# FLASH_S29GL256N11FFIV10_16Mx16.net
KiCad netlist of a schematic drawn in Altium Designer
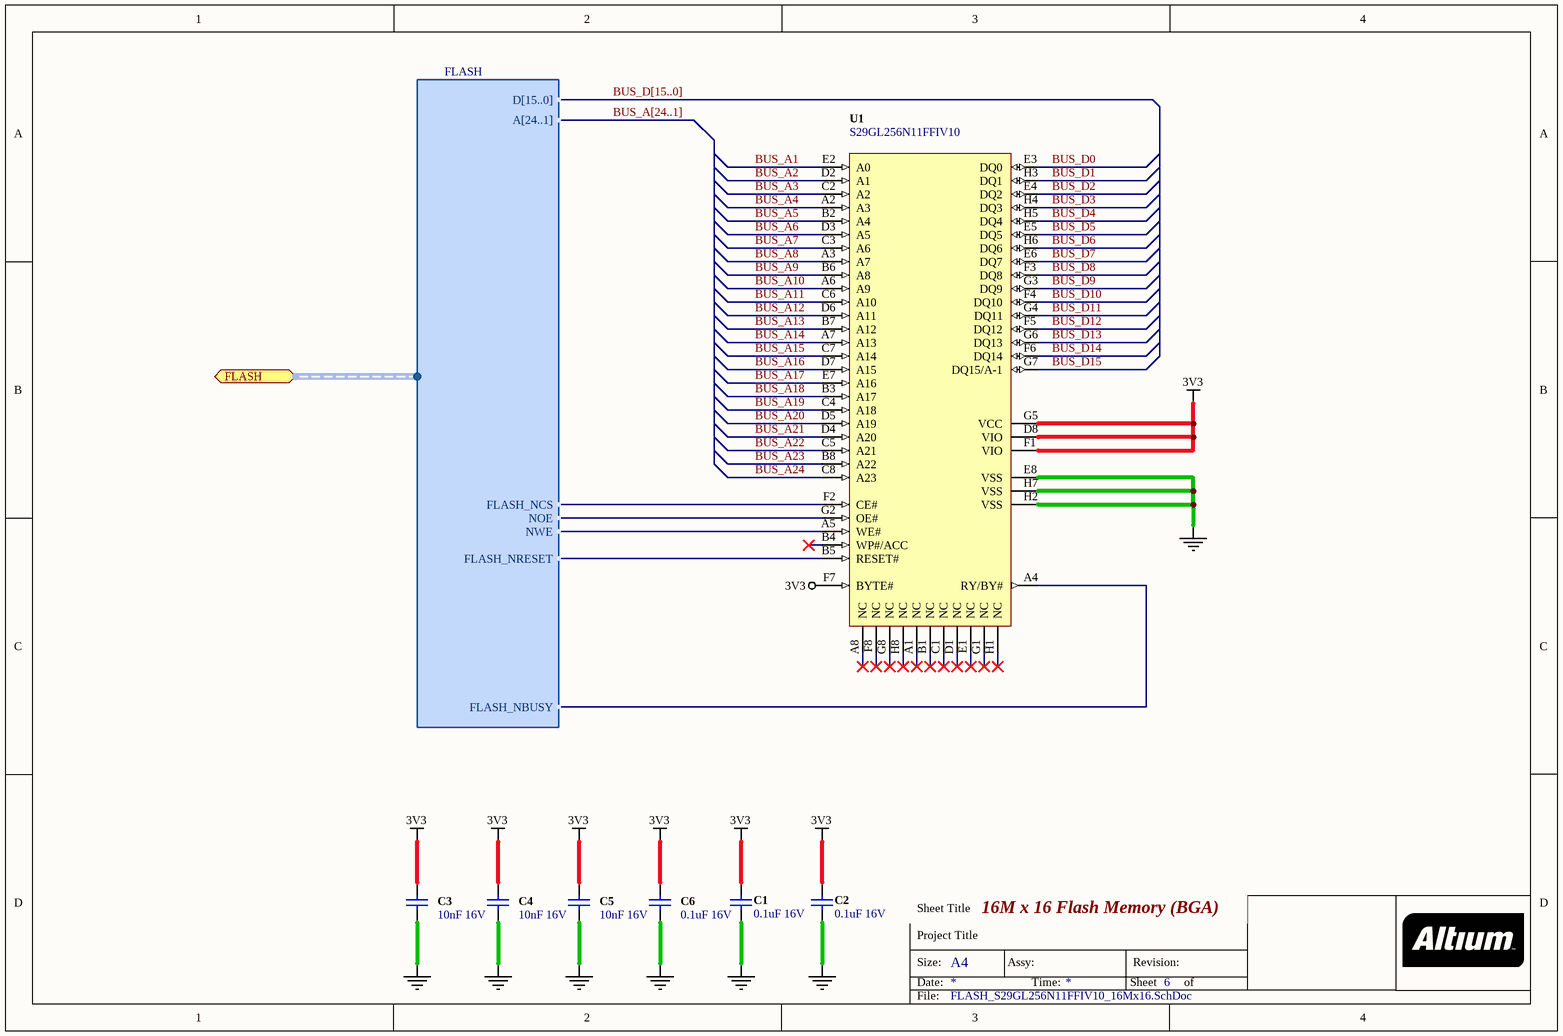
[diagram p0: FLASH_S29GL256N11FFIV10_16Mx16.SchDoc]

(export (version "E")
  (design (tool "Eeschema 10.0.6"))
  (components
    (comp (ref "C1")
      (value "0.1uF 16V")
      (footprint "CAPC1005-STAR")
      (description "Capacitor, Ceramic, 0.1uF 10% 16V 0402 (1005) X7R")
      (fields (field (name "TOLERANCE") "10 %"))
      (libsource (lib "altium-import") (part "root_0_mirrored_CAP-NP_"))
    )
    (comp (ref "C2")
      (value "0.1uF 16V")
      (footprint "CAPC1005-STAR")
      (description "Capacitor, Ceramic, 0.1uF 10% 16V 0402 (1005) X7R")
      (fields (field (name "TOLERANCE") "10 %"))
      (libsource (lib "altium-import") (part "root_0_mirrored_CAP-NP_"))
    )
    (comp (ref "C3")
      (value "10nF 16V")
      (footprint "CAPC1005-STAR")
      (description "Capacitor, Ceramic, 10nF 10% 16V 0402 (1005) X7R")
      (fields (field (name "TOLERANCE") "10 %"))
      (libsource (lib "altium-import") (part "root_0_CAP-NP_"))
    )
    (comp (ref "C4")
      (value "10nF 16V")
      (footprint "CAPC1005-STAR")
      (description "Capacitor, Ceramic, 10nF 10% 16V 0402 (1005) X7R")
      (fields (field (name "TOLERANCE") "10 %"))
      (libsource (lib "altium-import") (part "root_0_CAP-NP_"))
    )
    (comp (ref "C5")
      (value "10nF 16V")
      (footprint "CAPC1005-STAR")
      (description "Capacitor, Ceramic, 10nF 10% 16V 0402 (1005) X7R")
      (fields (field (name "TOLERANCE") "10 %"))
      (libsource (lib "altium-import") (part "root_0_CAP-NP_"))
    )
    (comp (ref "C6")
      (value "0.1uF 16V")
      (footprint "CAPC1005-STAR")
      (description "Capacitor, Ceramic, 0.1uF 10% 16V 0402 (1005) X7R")
      (fields (field (name "TOLERANCE") "10 %"))
      (libsource (lib "altium-import") (part "root_0_CAP-NP_"))
    )
    (comp (ref "U1")
      (value "S29GL256N11FFIV10")
      (footprint "BGA100P8X8-64")
      (description "S29GL256N11FFIV10, 256 Megabit (16M x 16) 3.0V Page Mode Flash Memory")
      (libsource (lib "altium-import") (part "root_0_S29GL256NF_"))
    )
  )
  (nets
    (net (code "2") (name "/BUS_A1") (class "Default")
      (node (ref "U1") (pin "E2") (pinfunction "A0_E2") (pintype "input"))
    )
    (net (code "3") (name "/BUS_A2") (class "Default")
      (node (ref "U1") (pin "D2") (pinfunction "A1_D2") (pintype "input"))
    )
    (net (code "4") (name "/BUS_A3") (class "Default")
      (node (ref "U1") (pin "C2") (pinfunction "A2_C2") (pintype "input"))
    )
    (net (code "5") (name "/BUS_A4") (class "Default")
      (node (ref "U1") (pin "A2") (pinfunction "A3_A2") (pintype "input"))
    )
    (net (code "6") (name "/BUS_A5") (class "Default")
      (node (ref "U1") (pin "B2") (pinfunction "A4_B2") (pintype "input"))
    )
    (net (code "7") (name "/BUS_A6") (class "Default")
      (node (ref "U1") (pin "D3") (pinfunction "A5_D3") (pintype "input"))
    )
    (net (code "8") (name "/BUS_A7") (class "Default")
      (node (ref "U1") (pin "C3") (pinfunction "A6_C3") (pintype "input"))
    )
    (net (code "9") (name "/BUS_A8") (class "Default")
      (node (ref "U1") (pin "A3") (pinfunction "A7_A3") (pintype "input"))
    )
    (net (code "10") (name "/BUS_A9") (class "Default")
      (node (ref "U1") (pin "B6") (pinfunction "A8_B6") (pintype "input"))
    )
    (net (code "11") (name "/BUS_A10") (class "Default")
      (node (ref "U1") (pin "A6") (pinfunction "A9_A6") (pintype "input"))
    )
    (net (code "12") (name "/BUS_A11") (class "Default")
      (node (ref "U1") (pin "C6") (pinfunction "A10_C6") (pintype "input"))
    )
    (net (code "13") (name "/BUS_A12") (class "Default")
      (node (ref "U1") (pin "D6") (pinfunction "A11_D6") (pintype "input"))
    )
    (net (code "14") (name "/BUS_A13") (class "Default")
      (node (ref "U1") (pin "B7") (pinfunction "A12_B7") (pintype "input"))
    )
    (net (code "15") (name "/BUS_A14") (class "Default")
      (node (ref "U1") (pin "A7") (pinfunction "A13_A7") (pintype "input"))
    )
    (net (code "16") (name "/BUS_A15") (class "Default")
      (node (ref "U1") (pin "C7") (pinfunction "A14_C7") (pintype "input"))
    )
    (net (code "17") (name "/BUS_A16") (class "Default")
      (node (ref "U1") (pin "D7") (pinfunction "A15_D7") (pintype "input"))
    )
    (net (code "18") (name "/BUS_A17") (class "Default")
      (node (ref "U1") (pin "E7") (pinfunction "A16_E7") (pintype "input"))
    )
    (net (code "19") (name "/BUS_A18") (class "Default")
      (node (ref "U1") (pin "B3") (pinfunction "A17_B3") (pintype "input"))
    )
    (net (code "20") (name "/BUS_A19") (class "Default")
      (node (ref "U1") (pin "C4") (pinfunction "A18_C4") (pintype "input"))
    )
    (net (code "21") (name "/BUS_A20") (class "Default")
      (node (ref "U1") (pin "D5") (pinfunction "A19_D5") (pintype "input"))
    )
    (net (code "22") (name "/BUS_A21") (class "Default")
      (node (ref "U1") (pin "D4") (pinfunction "A20_D4") (pintype "input"))
    )
    (net (code "23") (name "/BUS_A22") (class "Default")
      (node (ref "U1") (pin "C5") (pinfunction "A21_C5") (pintype "input"))
    )
    (net (code "24") (name "/BUS_A23") (class "Default")
      (node (ref "U1") (pin "B8") (pinfunction "A22_B8") (pintype "input"))
    )
    (net (code "25") (name "/BUS_A24") (class "Default")
      (node (ref "U1") (pin "C8") (pinfunction "A23_C8") (pintype "input"))
    )
    (net (code "27") (name "/BUS_D0") (class "Default")
      (node (ref "U1") (pin "E3") (pinfunction "DQ0_E3") (pintype "bidirectional"))
    )
    (net (code "28") (name "/BUS_D1") (class "Default")
      (node (ref "U1") (pin "H3") (pinfunction "DQ1_H3") (pintype "bidirectional"))
    )
    (net (code "29") (name "/BUS_D2") (class "Default")
      (node (ref "U1") (pin "E4") (pinfunction "DQ2_E4") (pintype "bidirectional"))
    )
    (net (code "30") (name "/BUS_D3") (class "Default")
      (node (ref "U1") (pin "H4") (pinfunction "DQ3_H4") (pintype "bidirectional"))
    )
    (net (code "31") (name "/BUS_D4") (class "Default")
      (node (ref "U1") (pin "H5") (pinfunction "DQ4_H5") (pintype "bidirectional"))
    )
    (net (code "32") (name "/BUS_D5") (class "Default")
      (node (ref "U1") (pin "E5") (pinfunction "DQ5_E5") (pintype "bidirectional"))
    )
    (net (code "33") (name "/BUS_D6") (class "Default")
      (node (ref "U1") (pin "H6") (pinfunction "DQ6_H6") (pintype "bidirectional"))
    )
    (net (code "34") (name "/BUS_D7") (class "Default")
      (node (ref "U1") (pin "E6") (pinfunction "DQ7_E6") (pintype "bidirectional"))
    )
    (net (code "35") (name "/BUS_D8") (class "Default")
      (node (ref "U1") (pin "F3") (pinfunction "DQ8_F3") (pintype "bidirectional"))
    )
    (net (code "36") (name "/BUS_D9") (class "Default")
      (node (ref "U1") (pin "G3") (pinfunction "DQ9_G3") (pintype "bidirectional"))
    )
    (net (code "37") (name "/BUS_D10") (class "Default")
      (node (ref "U1") (pin "F4") (pinfunction "DQ10_F4") (pintype "bidirectional"))
    )
    (net (code "38") (name "/BUS_D11") (class "Default")
      (node (ref "U1") (pin "G4") (pinfunction "DQ11_G4") (pintype "bidirectional"))
    )
    (net (code "39") (name "/BUS_D12") (class "Default")
      (node (ref "U1") (pin "F5") (pinfunction "DQ12_F5") (pintype "bidirectional"))
    )
    (net (code "40") (name "/BUS_D13") (class "Default")
      (node (ref "U1") (pin "G6") (pinfunction "DQ13_G6") (pintype "bidirectional"))
    )
    (net (code "41") (name "/BUS_D14") (class "Default")
      (node (ref "U1") (pin "F6") (pinfunction "DQ14_F6") (pintype "bidirectional"))
    )
    (net (code "42") (name "/BUS_D15") (class "Default")
      (node (ref "U1") (pin "G7") (pinfunction "DQ15/A-1_G7") (pintype "bidirectional"))
    )
    (net (code "44") (name "/FLASH_NBUSY") (class "Default")
      (node (ref "U1") (pin "A4") (pinfunction "RY/BY#_A4") (pintype "output"))
    )
    (net (code "45") (name "/FLASH_NCS") (class "Default")
      (node (ref "U1") (pin "F2") (pinfunction "CE#_F2") (pintype "input"))
    )
    (net (code "46") (name "/FLASH_NRESET") (class "Default")
      (node (ref "U1") (pin "B5") (pinfunction "RESET#_B5") (pintype "input"))
    )
    (net (code "47") (name "/NOE") (class "Default")
      (node (ref "U1") (pin "G2") (pinfunction "OE#_G2") (pintype "input"))
    )
    (net (code "48") (name "/NWE") (class "Default")
      (node (ref "U1") (pin "A5") (pinfunction "WE#_A5") (pintype "input"))
    )
    (net (code "50") (name "3V3") (class "Default")
      (node (ref "C1") (pin "1") (pinfunction "1_1") (pintype "passive"))
      (node (ref "C2") (pin "1") (pinfunction "1_1") (pintype "passive"))
      (node (ref "C3") (pin "1") (pinfunction "1_1") (pintype "passive"))
      (node (ref "C4") (pin "1") (pinfunction "1_1") (pintype "passive"))
      (node (ref "C5") (pin "1") (pinfunction "1_1") (pintype "passive"))
      (node (ref "C6") (pin "1") (pinfunction "1_1") (pintype "passive"))
      (node (ref "U1") (pin "D8") (pinfunction "VIO_D8") (pintype "power_in"))
      (node (ref "U1") (pin "F1") (pinfunction "VIO_F1") (pintype "power_in"))
      (node (ref "U1") (pin "F7") (pinfunction "BYTE#_F7") (pintype "input"))
      (node (ref "U1") (pin "G5") (pinfunction "VCC_G5") (pintype "power_in"))
    )
    (net (code "51") (name "GND") (class "Default")
      (node (ref "C1") (pin "2") (pinfunction "2_2") (pintype "passive"))
      (node (ref "C2") (pin "2") (pinfunction "2_2") (pintype "passive"))
      (node (ref "C3") (pin "2") (pinfunction "2_2") (pintype "passive"))
      (node (ref "C4") (pin "2") (pinfunction "2_2") (pintype "passive"))
      (node (ref "C5") (pin "2") (pinfunction "2_2") (pintype "passive"))
      (node (ref "C6") (pin "2") (pinfunction "2_2") (pintype "passive"))
      (node (ref "U1") (pin "E8") (pinfunction "VSS_E8") (pintype "power_in"))
      (node (ref "U1") (pin "H2") (pinfunction "VSS_H2") (pintype "power_in"))
      (node (ref "U1") (pin "H7") (pinfunction "VSS_H7") (pintype "power_in"))
    )
    (net (code "52") (name "unconnected-(U1-NC-PadA1)") (class "Default")
      (node (ref "U1") (pin "A1") (pinfunction "NC_A1") (pintype "passive+no_connect"))
    )
    (net (code "53") (name "unconnected-(U1-NC-PadA8)") (class "Default")
      (node (ref "U1") (pin "A8") (pinfunction "NC_A8") (pintype "passive+no_connect"))
    )
    (net (code "54") (name "unconnected-(U1-NC-PadB1)") (class "Default")
      (node (ref "U1") (pin "B1") (pinfunction "NC_B1") (pintype "passive+no_connect"))
    )
    (net (code "55") (name "unconnected-(U1-NC-PadC1)") (class "Default")
      (node (ref "U1") (pin "C1") (pinfunction "NC_C1") (pintype "passive+no_connect"))
    )
    (net (code "56") (name "unconnected-(U1-NC-PadD1)") (class "Default")
      (node (ref "U1") (pin "D1") (pinfunction "NC_D1") (pintype "passive+no_connect"))
    )
    (net (code "57") (name "unconnected-(U1-NC-PadE1)") (class "Default")
      (node (ref "U1") (pin "E1") (pinfunction "NC_E1") (pintype "passive+no_connect"))
    )
    (net (code "58") (name "unconnected-(U1-NC-PadF8)") (class "Default")
      (node (ref "U1") (pin "F8") (pinfunction "NC_F8") (pintype "passive+no_connect"))
    )
    (net (code "59") (name "unconnected-(U1-NC-PadG1)") (class "Default")
      (node (ref "U1") (pin "G1") (pinfunction "NC_G1") (pintype "passive+no_connect"))
    )
    (net (code "60") (name "unconnected-(U1-NC-PadG8)") (class "Default")
      (node (ref "U1") (pin "G8") (pinfunction "NC_G8") (pintype "passive+no_connect"))
    )
    (net (code "61") (name "unconnected-(U1-NC-PadH1)") (class "Default")
      (node (ref "U1") (pin "H1") (pinfunction "NC_H1") (pintype "passive+no_connect"))
    )
    (net (code "62") (name "unconnected-(U1-NC-PadH8)") (class "Default")
      (node (ref "U1") (pin "H8") (pinfunction "NC_H8") (pintype "passive+no_connect"))
    )
    (net (code "63") (name "unconnected-(U1-WP#{slash}ACC-PadB4)") (class "Default")
      (node (ref "U1") (pin "B4") (pinfunction "WP#/ACC_B4") (pintype "input+no_connect"))
    )
  )
)
